# Laser_Terminal.net
KiCad netlist of a schematic drawn in EAGLE
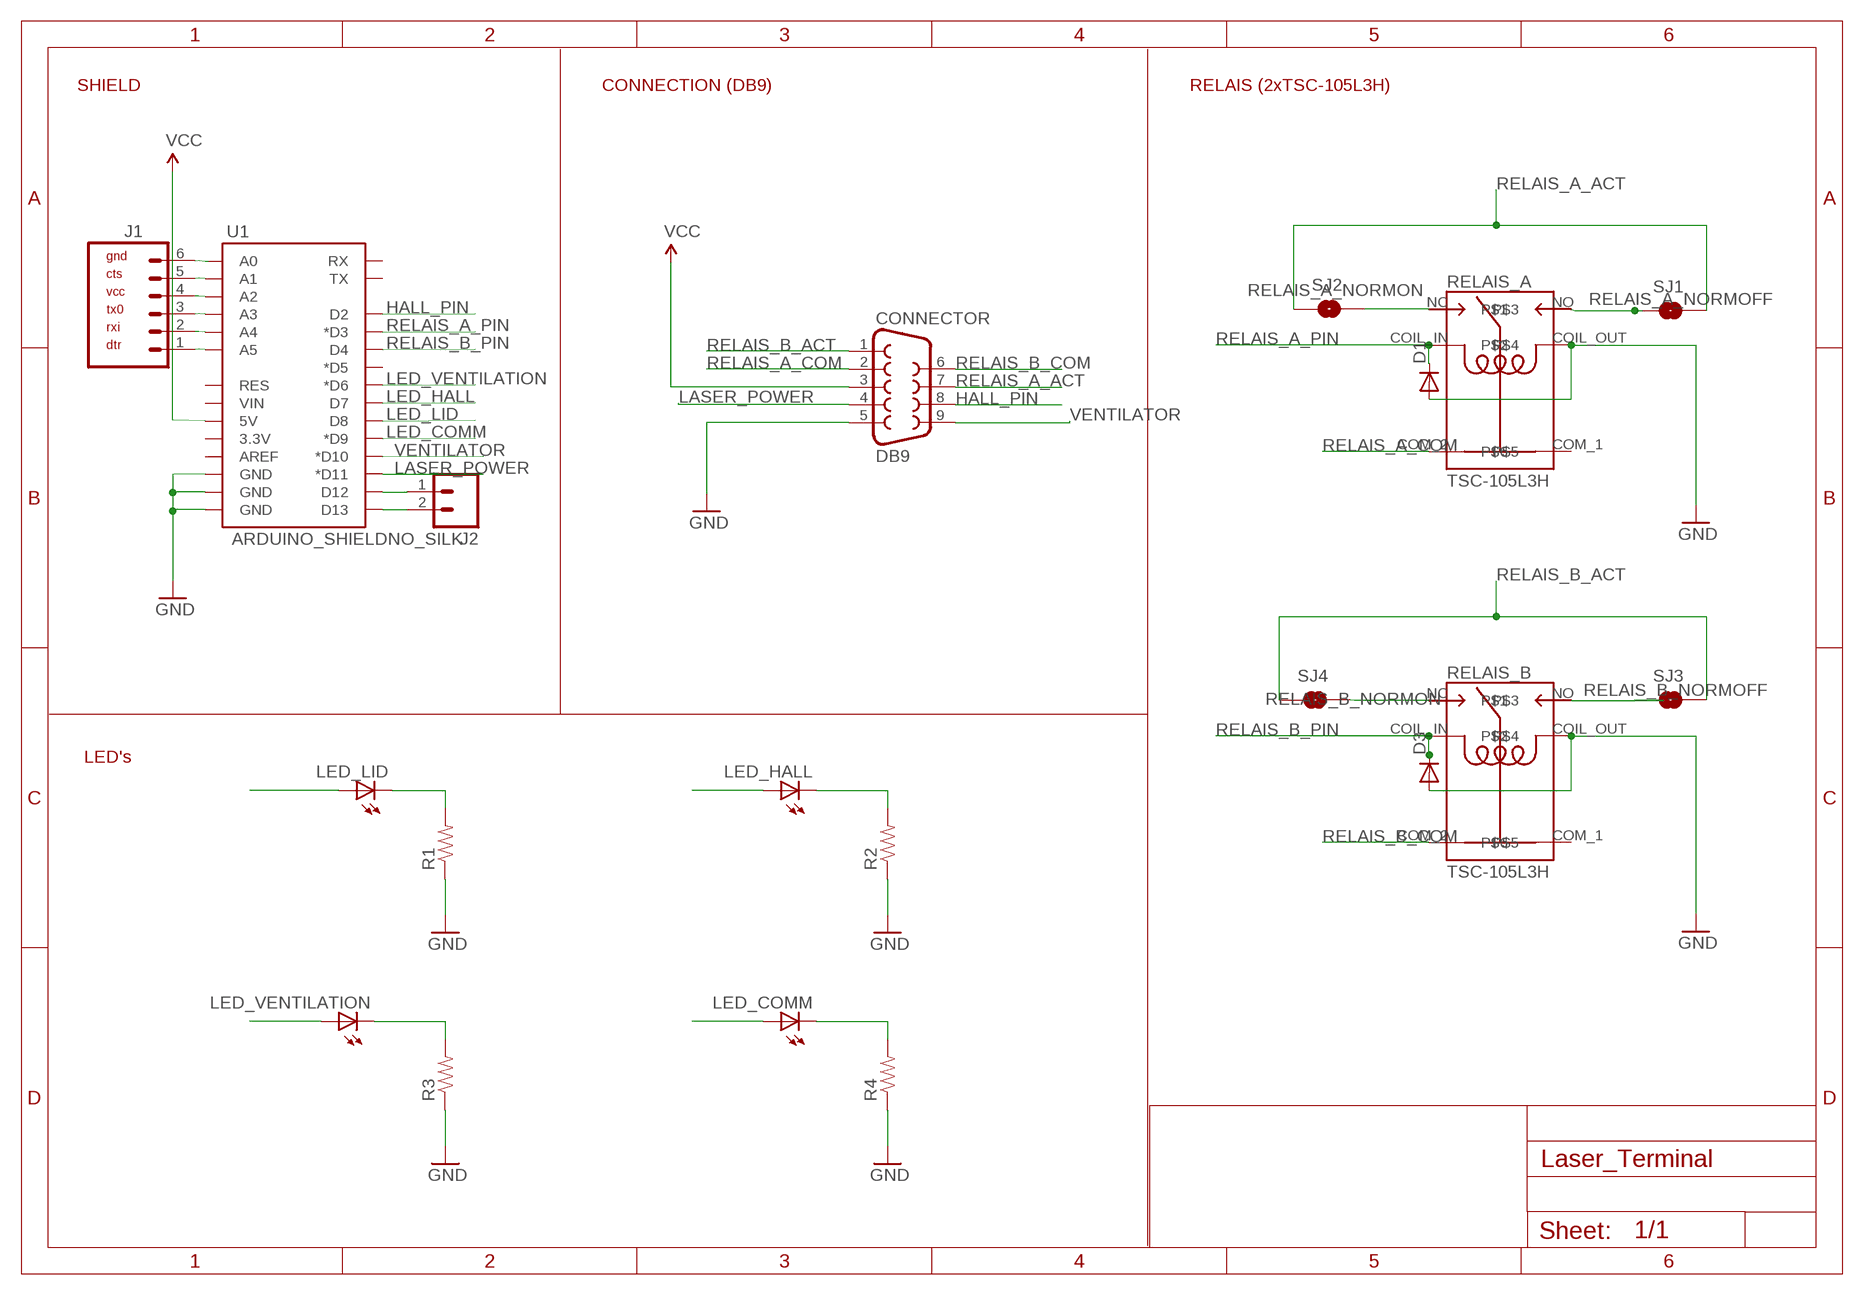
[diagram p0: schematic, sheet 1]

(export (version "E")
  (design (tool "Eeschema 10.0.6"))
  (components
    (comp (ref "CONNECTOR")
      (value "DB9")
      (footprint "eagle-import:DB9_MALE")
      (libsource (lib "eagle-import") (part "DB9MALE"))
    )
    (comp (ref "D1")
      (value "DIODEPTH")
      (footprint "eagle-import:DIODE-1N4001")
      (libsource (lib "eagle-import") (part "DIODEPTH"))
    )
    (comp (ref "D3")
      (value "DIODEPTH")
      (footprint "eagle-import:DIODE-1N4001")
      (libsource (lib "eagle-import") (part "DIODEPTH"))
    )
    (comp (ref "J1")
      (value "M06NO_SILK_YES_STOP")
      (footprint "eagle-import:1X06_NO_SILK_YES_STOP")
      (libsource (lib "eagle-import") (part "M06NO_SILK_YES_STOP"))
    )
    (comp (ref "J2")
      (value "M021X02_NO_SILK")
      (footprint "eagle-import:1X02_NO_SILK")
      (libsource (lib "eagle-import") (part "M021X02_NO_SILK"))
    )
    (comp (ref "LED_COMM")
      (value "LED5MM")
      (footprint "eagle-import:LED5MM")
      (libsource (lib "eagle-import") (part "LED5MM"))
    )
    (comp (ref "LED_HALL")
      (value "LED5MM")
      (footprint "eagle-import:LED5MM")
      (libsource (lib "eagle-import") (part "LED5MM"))
    )
    (comp (ref "LED_LID")
      (value "LED5MM")
      (footprint "eagle-import:LED5MM")
      (libsource (lib "eagle-import") (part "LED5MM"))
    )
    (comp (ref "LED_VENTILATION")
      (value "LED5MM")
      (footprint "eagle-import:LED5MM")
      (libsource (lib "eagle-import") (part "LED5MM"))
    )
    (comp (ref "R1")
      (value "RESISTORAXIAL-0.3")
      (footprint "eagle-import:AXIAL-0.3")
      (libsource (lib "eagle-import") (part "RESISTORAXIAL-0.3"))
    )
    (comp (ref "R2")
      (value "RESISTORAXIAL-0.3")
      (footprint "eagle-import:AXIAL-0.3")
      (libsource (lib "eagle-import") (part "RESISTORAXIAL-0.3"))
    )
    (comp (ref "R3")
      (value "RESISTORAXIAL-0.3")
      (footprint "eagle-import:AXIAL-0.3")
      (libsource (lib "eagle-import") (part "RESISTORAXIAL-0.3"))
    )
    (comp (ref "R4")
      (value "RESISTORAXIAL-0.3")
      (footprint "eagle-import:AXIAL-0.3")
      (libsource (lib "eagle-import") (part "RESISTORAXIAL-0.3"))
    )
    (comp (ref "RELAIS_A")
      (value "TSC-105L3H")
      (footprint "eagle-import:TSC_112L3H")
      (libsource (lib "eagle-import") (part "TSC-112L3H"))
    )
    (comp (ref "RELAIS_B")
      (value "TSC-105L3H")
      (footprint "eagle-import:TSC_112L3H")
      (libsource (lib "eagle-import") (part "TSC-112L3H"))
    )
    (comp (ref "SJ1")
      (value "SOLDERJUMPERNO")
      (footprint "eagle-import:SJ_2S-NO")
      (libsource (lib "eagle-import") (part "SOLDERJUMPERNO"))
    )
    (comp (ref "SJ2")
      (value "SOLDERJUMPERTRACE")
      (footprint "eagle-import:SJ_2S-TRACE")
      (libsource (lib "eagle-import") (part "SOLDERJUMPERTRACE"))
    )
    (comp (ref "SJ3")
      (value "SOLDERJUMPERNO")
      (footprint "eagle-import:SJ_2S-NO")
      (libsource (lib "eagle-import") (part "SOLDERJUMPERNO"))
    )
    (comp (ref "SJ4")
      (value "SOLDERJUMPERTRACE")
      (footprint "eagle-import:SJ_2S-TRACE")
      (libsource (lib "eagle-import") (part "SOLDERJUMPERTRACE"))
    )
    (comp (ref "U1")
      (value "ARDUINO_SHIELDNO_SILK")
      (footprint "eagle-import:DUEMILANOVE_VIAS")
      (libsource (lib "eagle-import") (part "ARDUINO_SHIELDNO_SILK"))
    )
  )
  (nets
    (net (code "1") (name "/HALL_PIN") (class "Default")
      (node (ref "CONNECTOR") (pin "8") (pinfunction "8_8") (pintype "passive"))
      (node (ref "U1") (pin "D2") (pinfunction "D2_D2") (pintype "bidirectional"))
    )
    (net (code "2") (name "/LASER_POWER") (class "Default")
      (node (ref "CONNECTOR") (pin "4") (pinfunction "4_4") (pintype "passive"))
      (node (ref "U1") (pin "D11") (pinfunction "*D11_D11") (pintype "bidirectional"))
    )
    (net (code "3") (name "/LED_COMM") (class "Default")
      (node (ref "LED_COMM") (pin "A") (pinfunction "A_A") (pintype "passive"))
      (node (ref "U1") (pin "D9") (pinfunction "*D9_D9") (pintype "bidirectional"))
    )
    (net (code "4") (name "/LED_HALL") (class "Default")
      (node (ref "LED_HALL") (pin "A") (pinfunction "A_A") (pintype "passive"))
      (node (ref "U1") (pin "D7") (pinfunction "D7_D7") (pintype "bidirectional"))
    )
    (net (code "5") (name "/LED_LID") (class "Default")
      (node (ref "LED_LID") (pin "A") (pinfunction "A_A") (pintype "passive"))
      (node (ref "U1") (pin "D8") (pinfunction "D8_D8") (pintype "bidirectional"))
    )
    (net (code "6") (name "/LED_VENTILATION") (class "Default")
      (node (ref "LED_VENTILATION") (pin "A") (pinfunction "A_A") (pintype "passive"))
      (node (ref "U1") (pin "D6") (pinfunction "*D6_D6") (pintype "bidirectional"))
    )
    (net (code "7") (name "/RELAIS_A_ACT") (class "Default")
      (node (ref "CONNECTOR") (pin "7") (pinfunction "7_7") (pintype "passive"))
      (node (ref "SJ1") (pin "2") (pinfunction "2_2") (pintype "passive"))
      (node (ref "SJ2") (pin "1") (pinfunction "1_1") (pintype "passive"))
    )
    (net (code "8") (name "/RELAIS_A_COM") (class "Default")
      (node (ref "CONNECTOR") (pin "2") (pinfunction "2_2") (pintype "passive"))
      (node (ref "RELAIS_A") (pin "COM_2") (pinfunction "P$6_COM_2") (pintype "bidirectional"))
    )
    (net (code "9") (name "/RELAIS_A_NORMOFF") (class "Default")
      (node (ref "RELAIS_A") (pin "NO") (pinfunction "P$3_NO") (pintype "bidirectional"))
      (node (ref "SJ1") (pin "1") (pinfunction "1_1") (pintype "passive"))
    )
    (net (code "10") (name "/RELAIS_A_NORMON") (class "Default")
      (node (ref "RELAIS_A") (pin "NC") (pinfunction "P$1_NC") (pintype "bidirectional"))
      (node (ref "SJ2") (pin "2") (pinfunction "2_2") (pintype "passive"))
    )
    (net (code "11") (name "/RELAIS_A_PIN") (class "Default")
      (node (ref "D1") (pin "C") (pinfunction "C_C") (pintype "passive"))
      (node (ref "RELAIS_A") (pin "COIL_IN") (pinfunction "P$2_COIL_IN") (pintype "bidirectional"))
      (node (ref "U1") (pin "D3") (pinfunction "*D3_D3") (pintype "bidirectional"))
    )
    (net (code "12") (name "/RELAIS_B_ACT") (class "Default")
      (node (ref "CONNECTOR") (pin "1") (pinfunction "1_1") (pintype "passive"))
      (node (ref "SJ3") (pin "2") (pinfunction "2_2") (pintype "passive"))
      (node (ref "SJ4") (pin "1") (pinfunction "1_1") (pintype "passive"))
    )
    (net (code "13") (name "/RELAIS_B_COM") (class "Default")
      (node (ref "CONNECTOR") (pin "6") (pinfunction "6_6") (pintype "passive"))
      (node (ref "RELAIS_B") (pin "COM_2") (pinfunction "P$6_COM_2") (pintype "bidirectional"))
    )
    (net (code "14") (name "/RELAIS_B_NORMOFF") (class "Default")
      (node (ref "RELAIS_B") (pin "NO") (pinfunction "P$3_NO") (pintype "bidirectional"))
      (node (ref "SJ3") (pin "1") (pinfunction "1_1") (pintype "passive"))
    )
    (net (code "15") (name "/RELAIS_B_NORMON") (class "Default")
      (node (ref "RELAIS_B") (pin "NC") (pinfunction "P$1_NC") (pintype "bidirectional"))
      (node (ref "SJ4") (pin "2") (pinfunction "2_2") (pintype "passive"))
    )
    (net (code "16") (name "/RELAIS_B_PIN") (class "Default")
      (node (ref "D3") (pin "C") (pinfunction "C_C") (pintype "passive"))
      (node (ref "RELAIS_B") (pin "COIL_IN") (pinfunction "P$2_COIL_IN") (pintype "bidirectional"))
      (node (ref "U1") (pin "D4") (pinfunction "D4_D4") (pintype "bidirectional"))
    )
    (net (code "17") (name "/VENTILATOR") (class "Default")
      (node (ref "CONNECTOR") (pin "9") (pinfunction "9_9") (pintype "passive"))
      (node (ref "U1") (pin "D10") (pinfunction "*D10_D10") (pintype "bidirectional"))
    )
    (net (code "18") (name "GND") (class "Default")
      (node (ref "CONNECTOR") (pin "5") (pinfunction "5_5") (pintype "passive"))
      (node (ref "D1") (pin "A") (pinfunction "A_A") (pintype "passive"))
      (node (ref "D3") (pin "A") (pinfunction "A_A") (pintype "passive"))
      (node (ref "R1") (pin "P$1") (pinfunction "1_P$1") (pintype "passive"))
      (node (ref "R2") (pin "P$1") (pinfunction "1_P$1") (pintype "passive"))
      (node (ref "R3") (pin "P$1") (pinfunction "1_P$1") (pintype "passive"))
      (node (ref "R4") (pin "P$1") (pinfunction "1_P$1") (pintype "passive"))
      (node (ref "RELAIS_A") (pin "COIL_OUT") (pinfunction "P$4_COIL_OUT") (pintype "bidirectional"))
      (node (ref "RELAIS_B") (pin "COIL_OUT") (pinfunction "P$4_COIL_OUT") (pintype "bidirectional"))
      (node (ref "U1") (pin "GND@0") (pinfunction "GND_GND@0") (pintype "bidirectional"))
      (node (ref "U1") (pin "GND@1") (pinfunction "GND_GND@1") (pintype "bidirectional"))
      (node (ref "U1") (pin "GND@2") (pinfunction "GND_GND@2") (pintype "bidirectional"))
    )
    (net (code "19") (name "Net-(J1-Pad1)") (class "Default")
      (node (ref "J1") (pin "1") (pinfunction "1_1") (pintype "passive"))
      (node (ref "U1") (pin "A5") (pinfunction "A5_A5") (pintype "bidirectional"))
    )
    (net (code "20") (name "Net-(J1-Pad2)") (class "Default")
      (node (ref "J1") (pin "2") (pinfunction "2_2") (pintype "passive"))
      (node (ref "U1") (pin "A4") (pinfunction "A4_A4") (pintype "bidirectional"))
    )
    (net (code "21") (name "Net-(J1-Pad3)") (class "Default")
      (node (ref "J1") (pin "3") (pinfunction "3_3") (pintype "passive"))
      (node (ref "U1") (pin "A3") (pinfunction "A3_A3") (pintype "bidirectional"))
    )
    (net (code "22") (name "Net-(J1-Pad4)") (class "Default")
      (node (ref "J1") (pin "4") (pinfunction "4_4") (pintype "passive"))
      (node (ref "U1") (pin "A2") (pinfunction "A2_A2") (pintype "bidirectional"))
    )
    (net (code "23") (name "Net-(J1-Pad5)") (class "Default")
      (node (ref "J1") (pin "5") (pinfunction "5_5") (pintype "passive"))
      (node (ref "U1") (pin "A1") (pinfunction "A1_A1") (pintype "bidirectional"))
    )
    (net (code "24") (name "Net-(J1-Pad6)") (class "Default")
      (node (ref "J1") (pin "6") (pinfunction "6_6") (pintype "passive"))
      (node (ref "U1") (pin "A0") (pinfunction "A0_A0") (pintype "bidirectional"))
    )
    (net (code "25") (name "Net-(J2-Pad1)") (class "Default")
      (node (ref "J2") (pin "1") (pinfunction "1_1") (pintype "passive"))
      (node (ref "U1") (pin "D12") (pinfunction "D12_D12") (pintype "bidirectional"))
    )
    (net (code "26") (name "Net-(J2-Pad2)") (class "Default")
      (node (ref "J2") (pin "2") (pinfunction "2_2") (pintype "passive"))
      (node (ref "U1") (pin "D13") (pinfunction "D13_D13") (pintype "bidirectional"))
    )
    (net (code "27") (name "Net-(LED_COMM-C)") (class "Default")
      (node (ref "LED_COMM") (pin "K") (pinfunction "C_K") (pintype "passive"))
      (node (ref "R4") (pin "P$2") (pinfunction "2_P$2") (pintype "passive"))
    )
    (net (code "28") (name "Net-(LED_HALL-C)") (class "Default")
      (node (ref "LED_HALL") (pin "K") (pinfunction "C_K") (pintype "passive"))
      (node (ref "R2") (pin "P$2") (pinfunction "2_P$2") (pintype "passive"))
    )
    (net (code "29") (name "Net-(LED_LID-C)") (class "Default")
      (node (ref "LED_LID") (pin "K") (pinfunction "C_K") (pintype "passive"))
      (node (ref "R1") (pin "P$2") (pinfunction "2_P$2") (pintype "passive"))
    )
    (net (code "30") (name "Net-(LED_VENTILATION-C)") (class "Default")
      (node (ref "LED_VENTILATION") (pin "K") (pinfunction "C_K") (pintype "passive"))
      (node (ref "R3") (pin "P$2") (pinfunction "2_P$2") (pintype "passive"))
    )
    (net (code "31") (name "VCC") (class "Default")
      (node (ref "CONNECTOR") (pin "3") (pinfunction "3_3") (pintype "passive"))
      (node (ref "U1") (pin "5V") (pinfunction "5V_5V") (pintype "bidirectional"))
    )
    (net (code "32") (name "unconnected-(RELAIS_A-P$5-PadCOM_1)") (class "Default")
      (node (ref "RELAIS_A") (pin "COM_1") (pinfunction "P$5_COM_1") (pintype "bidirectional"))
    )
    (net (code "33") (name "unconnected-(RELAIS_B-P$5-PadCOM_1)") (class "Default")
      (node (ref "RELAIS_B") (pin "COM_1") (pinfunction "P$5_COM_1") (pintype "bidirectional"))
    )
    (net (code "34") (name "unconnected-(U1-*D5-PadD5)") (class "Default")
      (node (ref "U1") (pin "D5") (pinfunction "*D5_D5") (pintype "bidirectional"))
    )
    (net (code "35") (name "unconnected-(U1-Pad3.3V)") (class "Default")
      (node (ref "U1") (pin "3.3V") (pinfunction "3.3V_3.3V") (pintype "bidirectional"))
    )
    (net (code "36") (name "unconnected-(U1-PadAREF)") (class "Default")
      (node (ref "U1") (pin "AREF") (pinfunction "AREF_AREF") (pintype "bidirectional"))
    )
    (net (code "37") (name "unconnected-(U1-PadRES)") (class "Default")
      (node (ref "U1") (pin "RES") (pinfunction "RES_RES") (pintype "bidirectional"))
    )
    (net (code "38") (name "unconnected-(U1-PadRX)") (class "Default")
      (node (ref "U1") (pin "RX") (pinfunction "RX_RX") (pintype "bidirectional"))
    )
    (net (code "39") (name "unconnected-(U1-PadTX)") (class "Default")
      (node (ref "U1") (pin "TX") (pinfunction "TX_TX") (pintype "bidirectional"))
    )
    (net (code "40") (name "unconnected-(U1-PadVIN)") (class "Default")
      (node (ref "U1") (pin "VIN") (pinfunction "VIN_VIN") (pintype "bidirectional"))
    )
  )
)
